# MIPI_MUX.net
KiCad netlist of a schematic drawn in Altium Designer
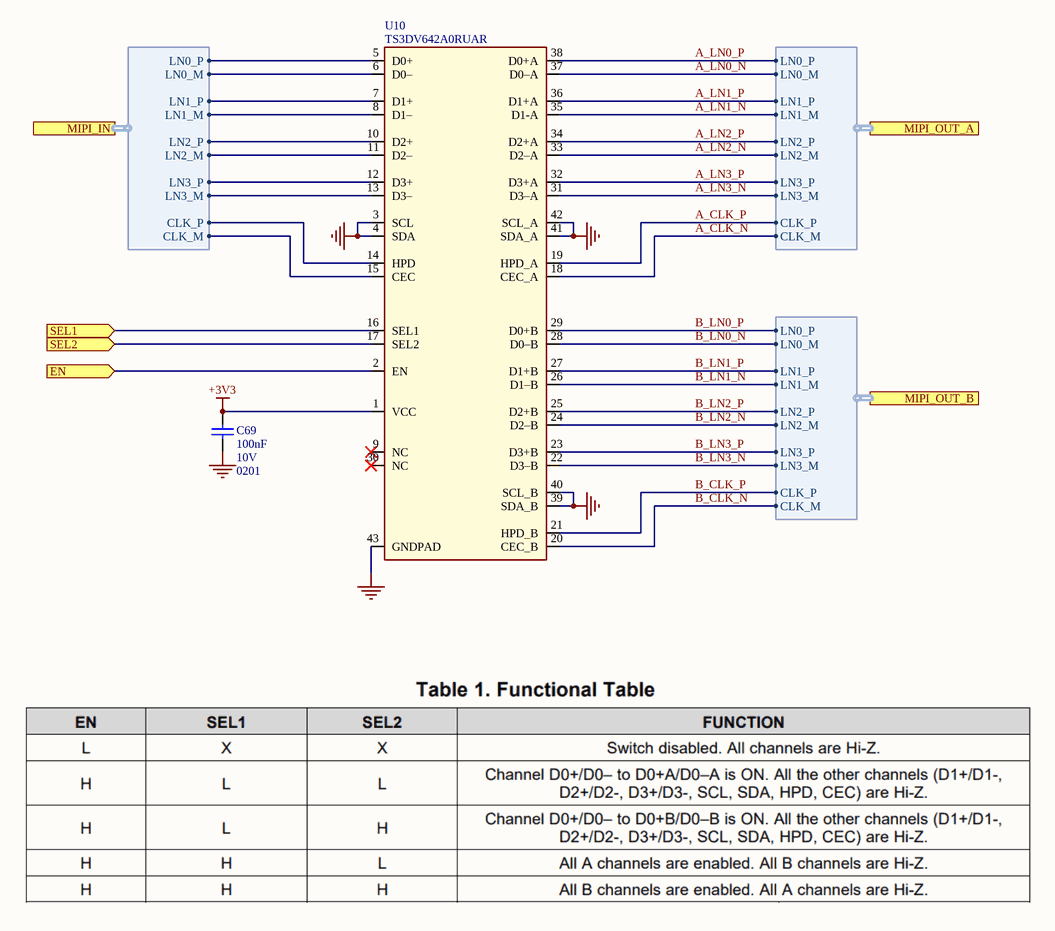
[diagram p0: MIPI_MUX.SchDoc]

(export (version "E")
  (design (tool "Eeschema 10.0.6"))
  (components
    (comp (ref "C69")
      (value "100nF")
      (footprint "CAP-0201")
      (description "CAP CHIP 0201 100nF 10% 10V X5R")
      (fields
        (field (name "PART NUMBER") "CL03A104KP3NNNC")
        (field (name "MANUFACTURER") "Samsung Electro-Mechanics")
        (field (name "VOLTAGE") "10V")
        (field (name "CASE CODE (IMPERIAL)") "0201")
      )
      (libsource (lib "Clean") (part "CAP"))
    )
    (comp (ref "U10")
      (value "TS3DV642A0RUAR")
      (footprint "TI RUA0042A WQFN 42 pin pitch 0.5mm 3.5x9mm")
      (fields (field (name "MANUFACTURER") "Texas Instruments"))
      (libsource (lib "Clean") (part "TS3DV642A0RUAR-Symbol-1"))
    )
  )
  (nets
    (net (code "2") (name "+3V3") (class "Default")
      (node (ref "C69") (pin "2") (pinfunction "2_2") (pintype "passive"))
      (node (ref "U10") (pin "1") (pinfunction "VCC_1") (pintype "passive"))
    )
    (net (code "3") (name "/A_CLK_N") (class "Default")
      (node (ref "U10") (pin "18") (pinfunction "CEC_A_18") (pintype "passive"))
    )
    (net (code "4") (name "/A_CLK_P") (class "Default")
      (node (ref "U10") (pin "19") (pinfunction "HPD_A_19") (pintype "passive"))
    )
    (net (code "5") (name "/A_LN0_N") (class "Default")
      (node (ref "U10") (pin "37") (pinfunction "D0–A_37") (pintype "passive"))
    )
    (net (code "6") (name "/A_LN0_P") (class "Default")
      (node (ref "U10") (pin "38") (pinfunction "D0+A_38") (pintype "passive"))
    )
    (net (code "7") (name "/A_LN1_N") (class "Default")
      (node (ref "U10") (pin "35") (pinfunction "D1-A_35") (pintype "passive"))
    )
    (net (code "8") (name "/A_LN1_P") (class "Default")
      (node (ref "U10") (pin "36") (pinfunction "D1+A_36") (pintype "passive"))
    )
    (net (code "9") (name "/A_LN2_N") (class "Default")
      (node (ref "U10") (pin "33") (pinfunction "D2–A_33") (pintype "passive"))
    )
    (net (code "10") (name "/A_LN2_P") (class "Default")
      (node (ref "U10") (pin "34") (pinfunction "D2+A_34") (pintype "passive"))
    )
    (net (code "11") (name "/A_LN3_N") (class "Default")
      (node (ref "U10") (pin "31") (pinfunction "D3–A_31") (pintype "passive"))
    )
    (net (code "12") (name "/A_LN3_P") (class "Default")
      (node (ref "U10") (pin "32") (pinfunction "D3+A_32") (pintype "passive"))
    )
    (net (code "13") (name "/B_CLK_N") (class "Default")
      (node (ref "U10") (pin "20") (pinfunction "CEC_B_20") (pintype "passive"))
    )
    (net (code "14") (name "/B_CLK_P") (class "Default")
      (node (ref "U10") (pin "21") (pinfunction "HPD_B_21") (pintype "passive"))
    )
    (net (code "15") (name "/B_LN0_N") (class "Default")
      (node (ref "U10") (pin "28") (pinfunction "D0–B_28") (pintype "passive"))
    )
    (net (code "16") (name "/B_LN0_P") (class "Default")
      (node (ref "U10") (pin "29") (pinfunction "D0+B_29") (pintype "passive"))
    )
    (net (code "17") (name "/B_LN1_N") (class "Default")
      (node (ref "U10") (pin "26") (pinfunction "D1–B_26") (pintype "passive"))
    )
    (net (code "18") (name "/B_LN1_P") (class "Default")
      (node (ref "U10") (pin "27") (pinfunction "D1+B_27") (pintype "passive"))
    )
    (net (code "19") (name "/B_LN2_N") (class "Default")
      (node (ref "U10") (pin "24") (pinfunction "D2–B_24") (pintype "passive"))
    )
    (net (code "20") (name "/B_LN2_P") (class "Default")
      (node (ref "U10") (pin "25") (pinfunction "D2+B_25") (pintype "passive"))
    )
    (net (code "21") (name "/B_LN3_N") (class "Default")
      (node (ref "U10") (pin "22") (pinfunction "D3–B_22") (pintype "passive"))
    )
    (net (code "22") (name "/B_LN3_P") (class "Default")
      (node (ref "U10") (pin "23") (pinfunction "D3+B_23") (pintype "passive"))
    )
    (net (code "23") (name "/EN") (class "Default")
      (node (ref "U10") (pin "2") (pinfunction "EN_2") (pintype "passive"))
    )
    (net (code "24") (name "/SEL1") (class "Default")
      (node (ref "U10") (pin "16") (pinfunction "SEL1_16") (pintype "passive"))
    )
    (net (code "25") (name "/SEL2") (class "Default")
      (node (ref "U10") (pin "17") (pinfunction "SEL2_17") (pintype "passive"))
    )
    (net (code "27") (name "GND") (class "Default")
      (node (ref "C69") (pin "1") (pinfunction "1_1") (pintype "passive"))
      (node (ref "U10") (pin "3") (pinfunction "SCL_3") (pintype "passive"))
      (node (ref "U10") (pin "39") (pinfunction "SDA_B_39") (pintype "passive"))
      (node (ref "U10") (pin "4") (pinfunction "SDA_4") (pintype "passive"))
      (node (ref "U10") (pin "40") (pinfunction "SCL_B_40") (pintype "passive"))
      (node (ref "U10") (pin "41") (pinfunction "SDA_A_41") (pintype "passive"))
      (node (ref "U10") (pin "42") (pinfunction "SCL_A_42") (pintype "passive"))
      (node (ref "U10") (pin "43") (pinfunction "GNDPAD_43") (pintype "passive"))
    )
    (net (code "28") (name "unconnected-(U10-CEC-Pad15)") (class "Default")
      (node (ref "U10") (pin "15") (pinfunction "CEC_15") (pintype "passive"))
    )
    (net (code "29") (name "unconnected-(U10-D0+-Pad5)") (class "Default")
      (node (ref "U10") (pin "5") (pinfunction "D0+_5") (pintype "passive"))
    )
    (net (code "30") (name "unconnected-(U10-D0–-Pad6)") (class "Default")
      (node (ref "U10") (pin "6") (pinfunction "D0–_6") (pintype "passive"))
    )
    (net (code "31") (name "unconnected-(U10-D1+-Pad7)") (class "Default")
      (node (ref "U10") (pin "7") (pinfunction "D1+_7") (pintype "passive"))
    )
    (net (code "32") (name "unconnected-(U10-D1–-Pad8)") (class "Default")
      (node (ref "U10") (pin "8") (pinfunction "D1–_8") (pintype "passive"))
    )
    (net (code "33") (name "unconnected-(U10-D2+-Pad10)") (class "Default")
      (node (ref "U10") (pin "10") (pinfunction "D2+_10") (pintype "passive"))
    )
    (net (code "34") (name "unconnected-(U10-D2–-Pad11)") (class "Default")
      (node (ref "U10") (pin "11") (pinfunction "D2–_11") (pintype "passive"))
    )
    (net (code "35") (name "unconnected-(U10-D3+-Pad12)") (class "Default")
      (node (ref "U10") (pin "12") (pinfunction "D3+_12") (pintype "passive"))
    )
    (net (code "36") (name "unconnected-(U10-D3–-Pad13)") (class "Default")
      (node (ref "U10") (pin "13") (pinfunction "D3–_13") (pintype "passive"))
    )
    (net (code "37") (name "unconnected-(U10-HPD-Pad14)") (class "Default")
      (node (ref "U10") (pin "14") (pinfunction "HPD_14") (pintype "passive"))
    )
    (net (code "38") (name "unconnected-(U10-NC-Pad9)") (class "Default")
      (node (ref "U10") (pin "9") (pinfunction "NC_9") (pintype "passive+no_connect"))
    )
    (net (code "39") (name "unconnected-(U10-NC-Pad30)") (class "Default")
      (node (ref "U10") (pin "30") (pinfunction "NC_30") (pintype "passive+no_connect"))
    )
  )
)
